# Microcontrollers.net
KiCad netlist of a schematic drawn in Altium Designer
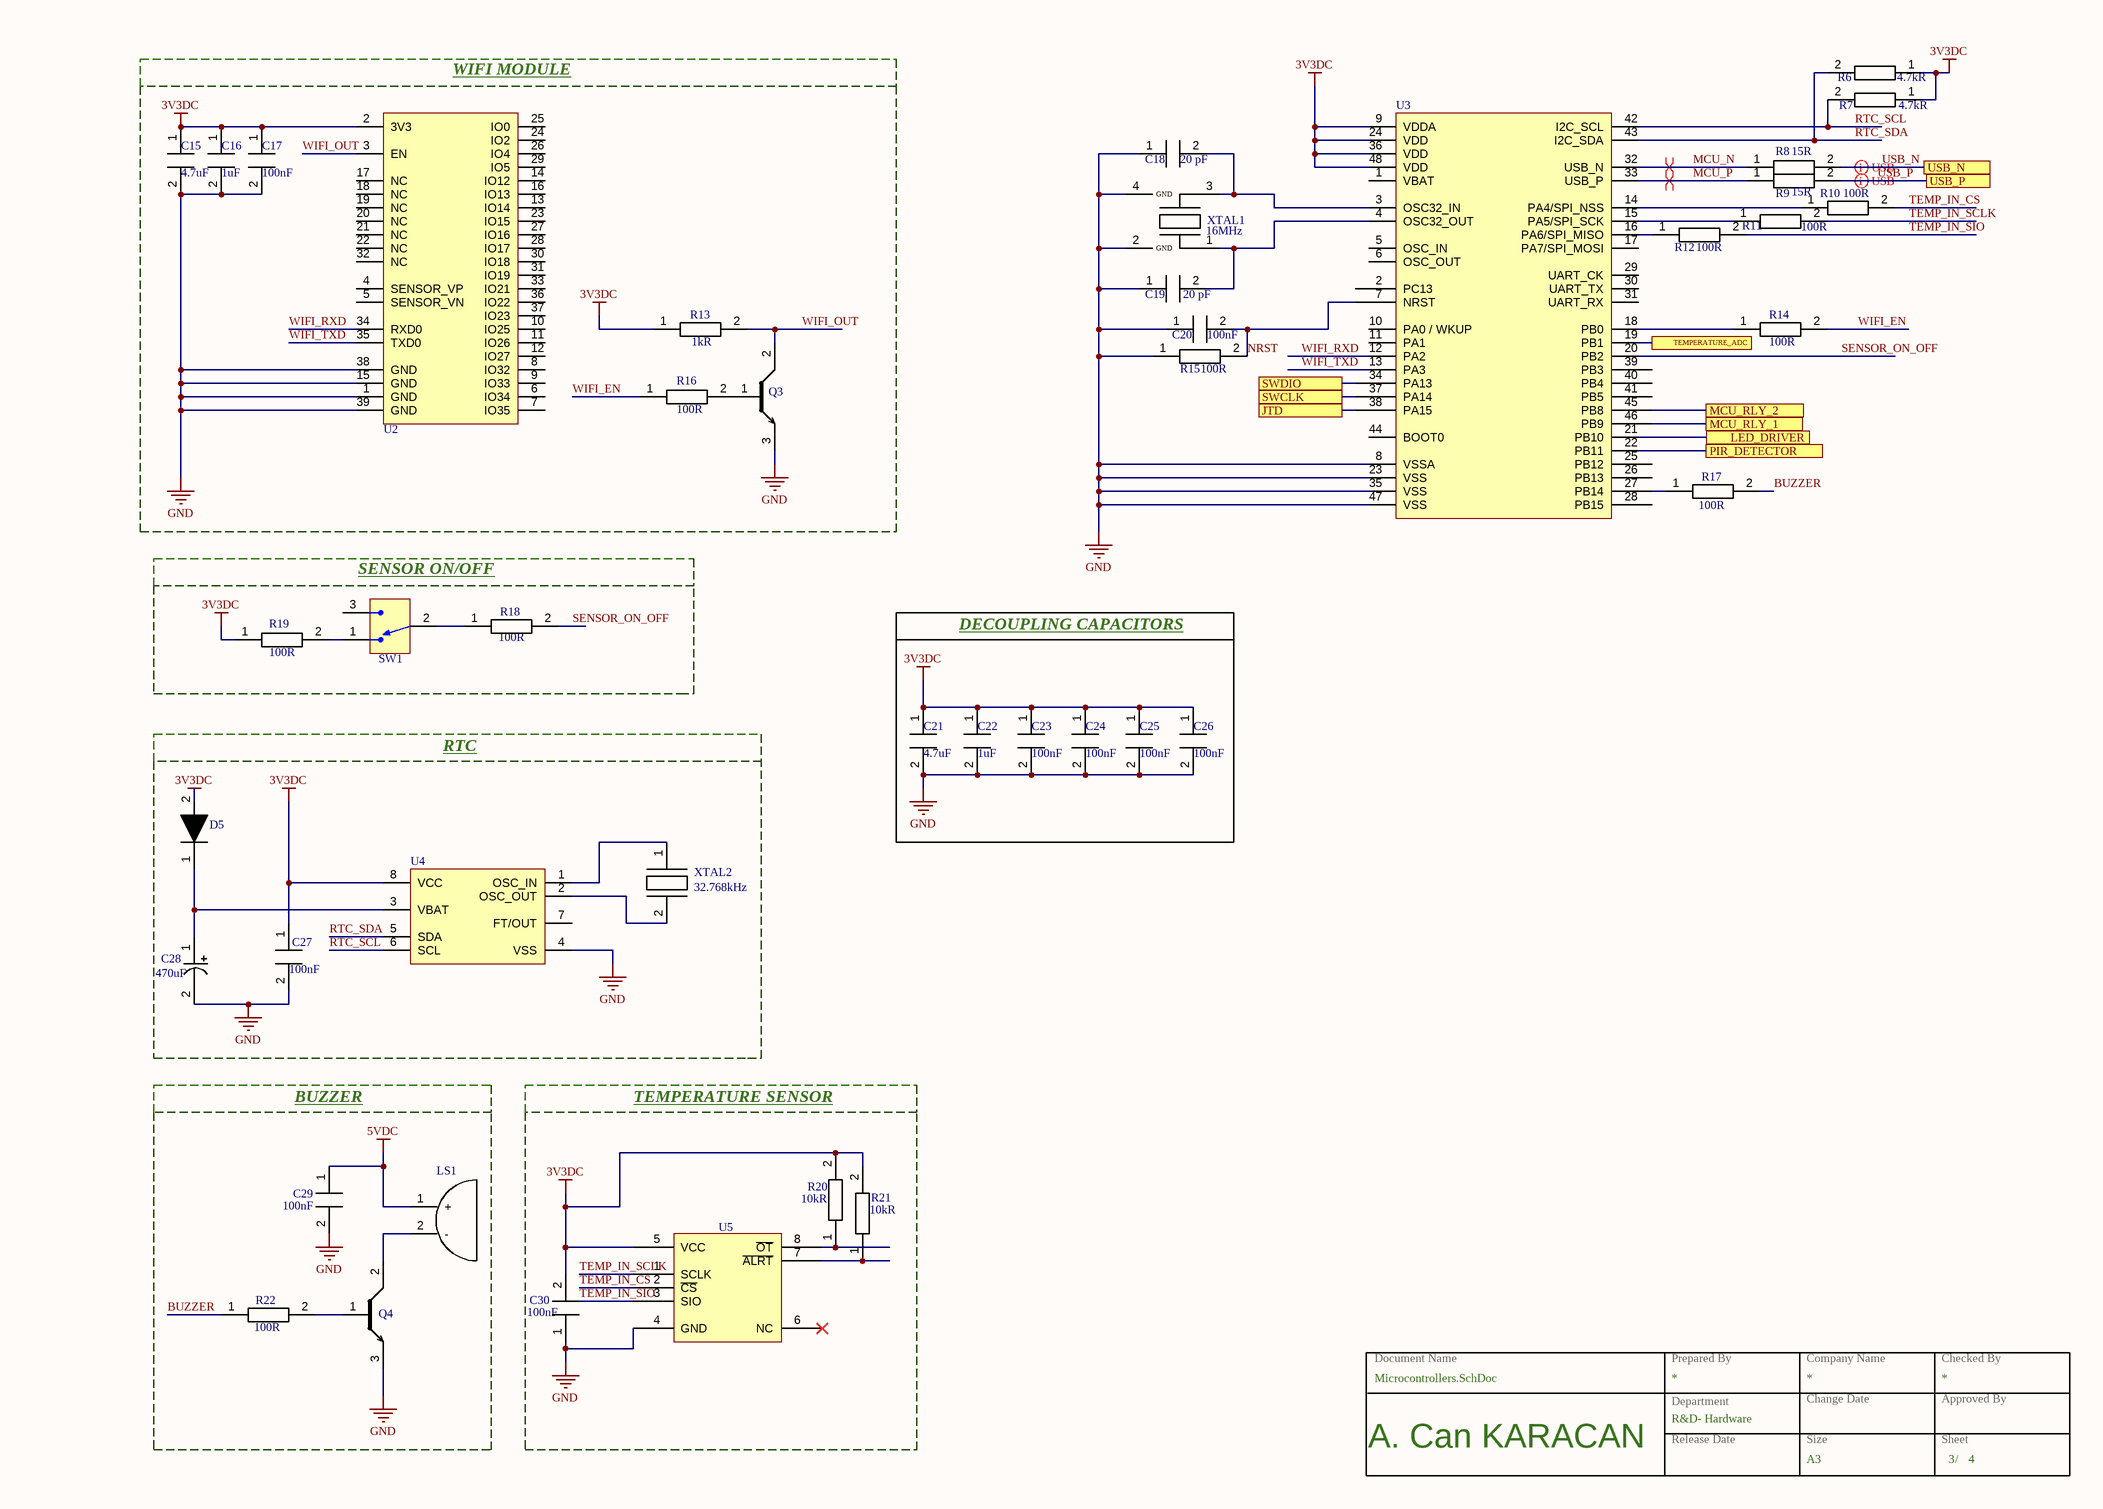
[diagram p0: Microcontrollers.SchDoc]

(export (version "E")
  (design (tool "Eeschema 10.0.6"))
  (components
    (comp (ref "C15")
      (value "4.7uF")
      (footprint "CAP_0805")
      (description "Multilayer Ceramic Capacitor, 4.7 uF, 25 V, ± 10%, X5R, 0805 [2012 Metric]")
      (fields
        (field (name "MANUFACTURER") "Samsung")
        (field (name "MANUFACTURER PART NUMBER") "CL21A475KAQNNNE")
        (field (name "DESIGNED BY") "Ahmet Can")
      )
      (libsource (lib "AHMET_CAN_KARACAN") (part "CAP CER 4.7uF 0805"))
    )
    (comp (ref "C16")
      (value "1uF")
      (footprint "CAP_0805")
      (description "CAP CER %10 1uF 0805")
      (fields
        (field (name "MANUFACTURER") "Samsung")
        (field (name "MANUFACTURER PART NUMBER") "CL21B105KBFNNNE")
      )
      (libsource (lib "AHMET_CAN_KARACAN") (part "CAP CER 1uF 0805"))
    )
    (comp (ref "C17")
      (value "CL21B104KBCNNNC")
      (footprint "CAP_0805")
      (description "Multilayer Ceramic Capacitor, 0.1 uF, 50 V, ± 10%, X7R, 0805 [2012 Metric]")
      (fields
        (field (name "MANUFACTURER") "Samsung")
        (field (name "TOLERANCE") "10%")
        (field (name "CAPACITANCE") "100nF")
      )
      (libsource (lib "AHMET_CAN_KARACAN") (part "CAP CER 100nF 0805"))
    )
    (comp (ref "C18")
      (value "20 pF")
      (footprint "CAP_0603")
      (description "CAP CER 20PF 50V C0G/NP0 0603")
      (fields
        (field (name "MANUFACTURER") "Samsung")
        (field (name "MANUFACTURER PART NUMBER") "CL10C200JB8NNNC")
        (field (name "DESIGNED BY") "Ahmet Can")
      )
      (libsource (lib "AHMET_CAN_KARACAN") (part "CAP CER 20pF 0603"))
    )
    (comp (ref "C19")
      (value "20 pF")
      (footprint "CAP_0603")
      (description "CAP CER 20PF 50V C0G/NP0 0603")
      (fields
        (field (name "MANUFACTURER") "Samsung")
        (field (name "MANUFACTURER PART NUMBER") "CL10C200JB8NNNC")
        (field (name "DESIGNED BY") "Ahmet Can")
      )
      (libsource (lib "AHMET_CAN_KARACAN") (part "CAP CER 20pF 0603"))
    )
    (comp (ref "C20")
      (value "104KBCNNNC")
      (footprint "CAP_0805")
      (description "Multilayer Ceramic Capacitor, 0.1 uF, 50 V, ± 10%, X7R, 0805 [2012 Metric]")
      (fields
        (field (name "MANUFACTURER") "Samsung")
        (field (name "MANUFACTURER PART NUMBER") "CL21B104KBCNNNC")
        (field (name "CAPACITANCE") "100nF")
      )
      (libsource (lib "AHMET_CAN_KARACAN") (part "CAP CER 100nF 0805"))
    )
    (comp (ref "C21")
      (value "4.7uF")
      (footprint "CAP_0805")
      (description "Multilayer Ceramic Capacitor, 4.7 uF, 25 V, ± 10%, X5R, 0805 [2012 Metric]")
      (fields
        (field (name "MANUFACTURER") "Samsung")
        (field (name "MANUFACTURER PART NUMBER") "CL21A475KAQNNNE")
        (field (name "DESIGNED BY") "Ahmet Can")
      )
      (libsource (lib "AHMET_CAN_KARACAN") (part "CAP CER 4.7uF 0805"))
    )
    (comp (ref "C22")
      (value "1uF")
      (footprint "CAP_0805")
      (description "CAP CER %10 1uF 0805")
      (fields
        (field (name "MANUFACTURER") "Samsung")
        (field (name "MANUFACTURER PART NUMBER") "CL21B105KBFNNNE")
      )
      (libsource (lib "AHMET_CAN_KARACAN") (part "CAP CER 1uF 0805"))
    )
    (comp (ref "C23")
      (value "CL21B104KBCNNNC")
      (footprint "CAP_0805")
      (description "Multilayer Ceramic Capacitor, 0.1 uF, 50 V, ± 10%, X7R, 0805 [2012 Metric]")
      (fields
        (field (name "MANUFACTURER") "Samsung")
        (field (name "TOLERANCE") "10%")
        (field (name "CAPACITANCE") "100nF")
      )
      (libsource (lib "AHMET_CAN_KARACAN") (part "CAP CER 100nF 0805"))
    )
    (comp (ref "C24")
      (value "CL21B104KBCNNNC")
      (footprint "CAP_0805")
      (description "Multilayer Ceramic Capacitor, 0.1 uF, 50 V, ± 10%, X7R, 0805 [2012 Metric]")
      (fields
        (field (name "MANUFACTURER") "Samsung")
        (field (name "TOLERANCE") "10%")
        (field (name "CAPACITANCE") "100nF")
      )
      (libsource (lib "AHMET_CAN_KARACAN") (part "CAP CER 100nF 0805"))
    )
    (comp (ref "C25")
      (value "CL21B104KBCNNNC")
      (footprint "CAP_0805")
      (description "Multilayer Ceramic Capacitor, 0.1 uF, 50 V, ± 10%, X7R, 0805 [2012 Metric]")
      (fields
        (field (name "MANUFACTURER") "Samsung")
        (field (name "TOLERANCE") "10%")
        (field (name "CAPACITANCE") "100nF")
      )
      (libsource (lib "AHMET_CAN_KARACAN") (part "CAP CER 100nF 0805"))
    )
    (comp (ref "C26")
      (value "CL21B104KBCNNNC")
      (footprint "CAP_0805")
      (description "Multilayer Ceramic Capacitor, 0.1 uF, 50 V, ± 10%, X7R, 0805 [2012 Metric]")
      (fields
        (field (name "MANUFACTURER") "Samsung")
        (field (name "TOLERANCE") "10%")
        (field (name "CAPACITANCE") "100nF")
      )
      (libsource (lib "AHMET_CAN_KARACAN") (part "CAP CER 100nF 0805"))
    )
    (comp (ref "C27")
      (value "CL21B104KBCNNNC")
      (footprint "CAP_0805")
      (description "Multilayer Ceramic Capacitor, 0.1 uF, 50 V, ± 10%, X7R, 0805 [2012 Metric]")
      (fields
        (field (name "MANUFACTURER") "Samsung")
        (field (name "TOLERANCE") "10%")
        (field (name "CAPACITANCE") "100nF")
        (field (name "DESIGNED BY") "Ahmet Can")
      )
      (libsource (lib "AHMET_CAN_KARACAN") (part "CAP CER 100nF 0805"))
    )
    (comp (ref "C28")
      (value "470uF")
      (footprint "CAP_RADIAL_D10_P5")
      (description "Cap, 470UF, 50V, Alu Elec, Radial, Through Hole")
      (fields
        (field (name "MANUFACTURER") "KEMET")
        (field (name "MANUFACTURER PART NUMBER") "ESH477M050AH4AA")
        (field (name "DESIGNED BY") "Ahmet Can")
      )
      (libsource (lib "AHMET_CAN_KARACAN") (part "CAP ALU ELEC 470uF"))
    )
    (comp (ref "C29")
      (value "CL21B104KBCNNNC")
      (footprint "CAP_0805")
      (description "Multilayer Ceramic Capacitor, 0.1 uF, 50 V, ± 10%, X7R, 0805 [2012 Metric]")
      (fields
        (field (name "MANUFACTURER") "Samsung")
        (field (name "TOLERANCE") "10%")
        (field (name "CAPACITANCE") "100nF")
        (field (name "DESIGNED BY") "Ahmet Can")
      )
      (libsource (lib "AHMET_CAN_KARACAN") (part "CAP CER 100nF 0805"))
    )
    (comp (ref "C30")
      (value "CL21B104KBCNNNC")
      (footprint "CAP_0805")
      (description "Multilayer Ceramic Capacitor, 0.1 uF, 50 V, ± 10%, X7R, 0805 [2012 Metric]")
      (fields
        (field (name "MANUFACTURER") "Samsung")
        (field (name "TOLERANCE") "10%")
        (field (name "CAPACITANCE") "100nF")
        (field (name "DESIGNED BY") "Ahmet Can")
      )
      (libsource (lib "AHMET_CAN_KARACAN") (part "CAP CER 100nF 0805"))
    )
    (comp (ref "D5")
      (value "1N4148WS")
      (footprint "SOD_323_F")
      (description "Diode Ultra Fast Recovery Rectifier 75V 0.15A 2-Pin SOD-323F T/R")
      (fields
        (field (name "MANUFACTURER") "ON Semiconductor / Fairchild")
        (field (name "DESIGNED BY") "Ahmet Can")
      )
      (libsource (lib "AHMET_CAN_KARACAN") (part "DIO_1N4148WS"))
    )
    (comp (ref "LS1")
      (value "CMI-9605-0580T")
      (footprint "CMI-9605")
      (description "9.6 mm, 5 Vdc, 80 dB, Through Hole, Driving Circuit, Magnetic Audio Indicator Buzzer")
      (fields (field (name "MANUFACTURER") "CUI") (field (name "DESIGNED BY") "Ahmet Can"))
      (libsource (lib "AHMET_CAN_KARACAN") (part "LS_CMI-9605-0580T"))
    )
    (comp (ref "Q3")
      (value "MMBT3904-7-F")
      (footprint "SOT_23_3")
      (description "Transistor General Purpose BJT NPN 40 Volt 0.2A Automotive 3-Pin SOT-23-3")
      (fields (field (name "MANUFACTURER") "Diodes Zetex") (field (name "DESIGNED BY") "Ahmet Can"))
      (libsource (lib "AHMET_CAN_KARACAN") (part "Q_MMBT3904-7-F"))
    )
    (comp (ref "Q4")
      (value "MMBT3904-7-F")
      (footprint "SOT_23_3")
      (description "Transistor General Purpose BJT NPN 40 Volt 0.2A Automotive 3-Pin SOT-23-3")
      (fields (field (name "MANUFACTURER") "Diodes Zetex") (field (name "DESIGNED BY") "Ahmet Can"))
      (libsource (lib "AHMET_CAN_KARACAN") (part "Q_MMBT3904-7-F"))
    )
    (comp (ref "R6")
      (value "4.7kR")
      (footprint "RE_0603")
      (description "SMD Chip Resistor, 4.7 kOhm, ± 5%, 100 mW, 0603 [1608 Metric], Thick Film, General Purpose")
      (fields
        (field (name "MANUFACTURER") "Yageo")
        (field (name "MANUFACTURER PART NUMBER") "RC0603JR-074K7L")
        (field (name "DESIGNED BY") "Ahmet Can")
      )
      (libsource (lib "AHMET_CAN_KARACAN") (part "RES 4K7 0603"))
    )
    (comp (ref "R7")
      (value "4.7kR")
      (footprint "RE_0603")
      (description "SMD Chip Resistor, 4.7 kOhm, ± 5%, 100 mW, 0603 [1608 Metric], Thick Film, General Purpose")
      (fields
        (field (name "MANUFACTURER") "Yageo")
        (field (name "MANUFACTURER PART NUMBER") "RC0603JR-074K7L")
        (field (name "DESIGNED BY") "Ahmet Can")
      )
      (libsource (lib "AHMET_CAN_KARACAN") (part "RES 4K7 0603"))
    )
    (comp (ref "R8")
      (value "15R")
      (footprint "RE_0603")
      (description "SMD Chip Resistor, 15 Ohm, ± 5%, 100 mW, 0603 [1608 Metric], Thick Film, General Purpose")
      (fields
        (field (name "MANUFACTURER") "Yageo")
        (field (name "MANUFACTURER PART NUMBER") "RC0603JR-0715RL")
        (field (name "DESIGNED BY") "Ahmet Can")
      )
      (libsource (lib "AHMET_CAN_KARACAN") (part "RES 15 0603"))
    )
    (comp (ref "R9")
      (value "15R")
      (footprint "RE_0603")
      (description "SMD Chip Resistor, 15 Ohm, ± 5%, 100 mW, 0603 [1608 Metric], Thick Film, General Purpose")
      (fields
        (field (name "MANUFACTURER") "Yageo")
        (field (name "MANUFACTURER PART NUMBER") "RC0603JR-0715RL")
        (field (name "DESIGNED BY") "Ahmet Can")
      )
      (libsource (lib "AHMET_CAN_KARACAN") (part "RES 15 0603"))
    )
    (comp (ref "R10")
      (value "100R")
      (footprint "RE_0603")
      (description "Res Thick Film 0603 100 Ohm 5% 1/10W ±100ppm/°C Molded SMD SMD Paper T/R")
      (fields
        (field (name "MANUFACTURER") "Yageo")
        (field (name "MANUFACTURER PART NUMBER") "RC0603JR-07100RL")
        (field (name "DESIGNED BY") "Ahmet Can")
      )
      (libsource (lib "AHMET_CAN_KARACAN") (part "RES 100 0603"))
    )
    (comp (ref "R11")
      (value "100R")
      (footprint "RE_0603")
      (description "Res Thick Film 0603 100 Ohm 5% 1/10W ±100ppm/°C Molded SMD SMD Paper T/R")
      (fields
        (field (name "MANUFACTURER") "Yageo")
        (field (name "MANUFACTURER PART NUMBER") "RC0603JR-07100RL")
        (field (name "DESIGNED BY") "Ahmet Can")
      )
      (libsource (lib "AHMET_CAN_KARACAN") (part "RES 100 0603"))
    )
    (comp (ref "R12")
      (value "100R")
      (footprint "RE_0603")
      (description "Res Thick Film 0603 100 Ohm 5% 1/10W ±100ppm/°C Molded SMD SMD Paper T/R")
      (fields
        (field (name "MANUFACTURER") "Yageo")
        (field (name "MANUFACTURER PART NUMBER") "RC0603JR-07100RL")
        (field (name "DESIGNED BY") "Ahmet Can")
      )
      (libsource (lib "AHMET_CAN_KARACAN") (part "RES 100 0603"))
    )
    (comp (ref "R13")
      (value "1kR")
      (footprint "RE_0603")
      (description "SMD Chip Resistor, 1 kOhm, ± 1%, 63 mW, 0402 [1005 Metric], Thick Film, General Purpose")
      (fields
        (field (name "MANUFACTURER") "Yageo")
        (field (name "MANUFACTURER PART NUMBER") "RC0402FR-071KL")
        (field (name "DESIGNED BY") "Ahmet Can")
      )
      (libsource (lib "AHMET_CAN_KARACAN") (part "RES 1K 0603"))
    )
    (comp (ref "R14")
      (value "100R")
      (footprint "RE_0603")
      (description "Res Thick Film 0603 100 Ohm 5% 1/10W ±100ppm/°C Molded SMD SMD Paper T/R")
      (fields
        (field (name "MANUFACTURER") "Yageo")
        (field (name "MANUFACTURER PART NUMBER") "RC0603JR-07100RL")
        (field (name "DESIGNED BY") "Ahmet Can")
      )
      (libsource (lib "AHMET_CAN_KARACAN") (part "RES 100 0603"))
    )
    (comp (ref "R15")
      (value "100R")
      (footprint "RE_0603")
      (description "Res Thick Film 0603 100 Ohm 5% 1/10W ±100ppm/°C Molded SMD SMD Paper T/R")
      (fields
        (field (name "MANUFACTURER") "Yageo")
        (field (name "MANUFACTURER PART NUMBER") "RC0603JR-07100RL")
        (field (name "DESIGNED BY") "Ahmet Can")
      )
      (libsource (lib "AHMET_CAN_KARACAN") (part "RES 100 0603"))
    )
    (comp (ref "R16")
      (value "100R")
      (footprint "RE_0603")
      (description "Res Thick Film 0603 100 Ohm 5% 1/10W ±100ppm/°C Molded SMD SMD Paper T/R")
      (fields
        (field (name "MANUFACTURER") "Yageo")
        (field (name "MANUFACTURER PART NUMBER") "RC0603JR-07100RL")
        (field (name "DESIGNED BY") "Ahmet Can")
      )
      (libsource (lib "AHMET_CAN_KARACAN") (part "RES 100 0603"))
    )
    (comp (ref "R17")
      (value "100R")
      (footprint "RE_0603")
      (description "Res Thick Film 0603 100 Ohm 5% 1/10W ±100ppm/°C Molded SMD SMD Paper T/R")
      (fields
        (field (name "MANUFACTURER") "Yageo")
        (field (name "MANUFACTURER PART NUMBER") "RC0603JR-07100RL")
        (field (name "DESIGNED BY") "Ahmet Can")
      )
      (libsource (lib "AHMET_CAN_KARACAN") (part "RES 100 0603"))
    )
    (comp (ref "R18")
      (value "100R")
      (footprint "RE_0603")
      (description "Res Thick Film 0603 100 Ohm 5% 1/10W ±100ppm/°C Molded SMD SMD Paper T/R")
      (fields
        (field (name "MANUFACTURER") "Yageo")
        (field (name "MANUFACTURER PART NUMBER") "RC0603JR-07100RL")
        (field (name "DESIGNED BY") "Ahmet Can")
      )
      (libsource (lib "AHMET_CAN_KARACAN") (part "RES 100 0603"))
    )
    (comp (ref "R19")
      (value "100R")
      (footprint "RE_0603")
      (description "Res Thick Film 0603 100 Ohm 5% 1/10W ±100ppm/°C Molded SMD SMD Paper T/R")
      (fields
        (field (name "MANUFACTURER") "Yageo")
        (field (name "MANUFACTURER PART NUMBER") "RC0603JR-07100RL")
        (field (name "DESIGNED BY") "Ahmet Can")
      )
      (libsource (lib "AHMET_CAN_KARACAN") (part "RES 100 0603"))
    )
    (comp (ref "R20")
      (value "10kR")
      (footprint "RE_0402")
      (description "SMD Chip Resistor, 10 kOhm, ± 5%, 63 mW, 0402 [1005 Metric], Thick Film, General Purpose")
      (fields
        (field (name "MANUFACTURER") "Yageo")
        (field (name "MANUFACTURER PART NUMBER") "RC0402JR-0710KL")
        (field (name "DESIGNED BY") "Ahmet Can")
      )
      (libsource (lib "AHMET_CAN_KARACAN") (part "RES 10K 0402"))
    )
    (comp (ref "R21")
      (value "10kR")
      (footprint "RE_0402")
      (description "SMD Chip Resistor, 10 kOhm, ± 5%, 63 mW, 0402 [1005 Metric], Thick Film, General Purpose")
      (fields
        (field (name "MANUFACTURER") "Yageo")
        (field (name "MANUFACTURER PART NUMBER") "RC0402JR-0710KL")
        (field (name "DESIGNED BY") "Ahmet Can")
      )
      (libsource (lib "AHMET_CAN_KARACAN") (part "RES 10K 0402"))
    )
    (comp (ref "R22")
      (value "100R")
      (footprint "RE_0603")
      (description "Res Thick Film 0603 100 Ohm 5% 1/10W ±100ppm/°C Molded SMD SMD Paper T/R")
      (fields
        (field (name "MANUFACTURER") "Yageo")
        (field (name "MANUFACTURER PART NUMBER") "RC0603JR-07100RL")
        (field (name "DESIGNED BY") "Ahmet Can")
      )
      (libsource (lib "AHMET_CAN_KARACAN") (part "RES 100 0603"))
    )
    (comp (ref "SW1")
      (value "EG1215AA")
      (footprint "EG1215AA")
      (description "Slide Switch, SPDT, 0.025A, 24V, SMD")
      (fields (field (name "MANUFACTURER") "E-Switch") (field (name "DESIGNED BY") "Ahmet Can"))
      (libsource (lib "AHMET_CAN_KARACAN") (part "SW_EG1215AA"))
    )
    (comp (ref "U2")
      (value "ESP32-WROOM-32E-N4")
      (footprint "38_SMD")
      (description "SMD module, ESP32-D0WD-V3, ESP32 ECO V3, 4 MB SPI flash, PCB antenna")
      (fields
        (field (name "MANUFACTURER") "Espressif Systems")
        (field (name "MANUFACTURER PART NUMBER") "ESP32-WROOM-32E(M113EH3200PH3Q0)")
        (field (name "DESIGNED BY") "Ahmet Can")
      )
      (libsource (lib "AHMET_CAN_KARACAN") (part "U_ESP32-WROOM-32E-N4"))
    )
    (comp (ref "U3")
      (value "STM32F103C6T6A")
      (footprint "LQGP48-STM")
      (description "MCU 32-bit STM32F ARM Cortex M3 RISC 32KB Flash 2.5V/3.3V 48-Pin LQFP Tray")
      (fields (field (name "MANUFACTURER") "STMicroelectronics") (field (name "DESIGNED BY") "Ahmet Can"))
      (libsource (lib "AHMET_CAN_KARACAN") (part "U_STM32F103C6T6A"))
    )
    (comp (ref "U4")
      (value "M41T0M6F")
      (footprint "8_SOIC")
      (description "M41T0 Series 2 to 5.5 V Serial I2C Real Time Clock Surface Mount - SOIC-8")
      (fields (field (name "MANUFACTURER") "STMicroelectronics") (field (name "DESIGNEDBY") "Ahmet Can"))
      (libsource (lib "AHMET_CAN_KARACAN") (part "RTC_M41T0M6F"))
    )
    (comp (ref "U5")
      (value "MAX6662MSA+")
      (footprint "8_SOIC")
      (description "Temp Sensor Digital Serial (3-Wire, SPI) 8-Pin SOIC N Tube")
      (fields (field (name "MANUFACTURER") "Maxim") (field (name "DESIGNED BY") "Ahmet Can"))
      (libsource (lib "AHMET_CAN_KARACAN") (part "U_MAX6662MSA+"))
    )
    (comp (ref "XTAL1")
      (value "ECS-160-20-30B-TR")
      (footprint "4-SMD, No Lead")
      (description "Crystal 16MHz ±30ppm (Tol) ±100ppm (Stability) 20pF FUND 50Ohm 4-Pin SMD T/R")
      (fields
        (field (name "MANUFACTURER") "ECS International")
        (field (name "MANUFACTURER PART NUMBER") "ECS-160-20-30B-DU")
        (field (name "FREQUENCY") "16MHz")
        (field (name "DESIGNED BY") "Ahmet Can")
      )
      (libsource (lib "AHMET_CAN_KARACAN") (part "XTAL_CRYSTAL 16 MHz"))
    )
    (comp (ref "XTAL2")
      (value "ABS05-32.768KHZ-T")
      (footprint "2-SMD, No Lead")
      (description "CRYSTAL 32.768kHz ±20ppm Crystal 12.5pF 90 kOhm -40°C ^ 85°C Surface Mount 2-SMD")
      (fields
        (field (name "MANUFACTURER") "Abracon")
        (field (name "TOLERANCE") "20ppm")
        (field (name "FREQUENCY") "32.768kHz")
        (field (name "DESIGNED BY") "Ahmet Can")
      )
      (libsource (lib "AHMET_CAN_KARACAN") (part "XTAL_CRYSTAL 32.768 KHz"))
    )
  )
  (nets
    (net (code "1") (name "/BUZZER") (class "Default")
      (node (ref "R17") (pin "2") (pintype "passive"))
      (node (ref "R22") (pin "1") (pintype "passive"))
    )
    (net (code "2") (name "/JTD") (class "Default")
      (node (ref "U3") (pin "38") (pinfunction "PA15_38") (pintype "passive"))
    )
    (net (code "3") (name "/LED_DRIVER") (class "Default")
      (node (ref "U3") (pin "21") (pinfunction "PB10_21") (pintype "passive"))
    )
    (net (code "4") (name "/MCU_N") (class "Default")
      (node (ref "R8") (pin "1") (pintype "passive"))
      (node (ref "U3") (pin "32") (pinfunction "USB_N_32") (pintype "passive"))
    )
    (net (code "5") (name "/MCU_P") (class "Default")
      (node (ref "R9") (pin "1") (pintype "passive"))
      (node (ref "U3") (pin "33") (pinfunction "USB_P_33") (pintype "passive"))
    )
    (net (code "6") (name "/MCU_RLY_1") (class "Default")
      (node (ref "U3") (pin "46") (pinfunction "PB9_46") (pintype "passive"))
    )
    (net (code "7") (name "/MCU_RLY_2") (class "Default")
      (node (ref "U3") (pin "45") (pinfunction "PB8_45") (pintype "passive"))
    )
    (net (code "8") (name "/NRST") (class "Default")
      (node (ref "C20") (pin "2") (pintype "passive"))
      (node (ref "R15") (pin "2") (pintype "passive"))
      (node (ref "U3") (pin "7") (pinfunction "NRST_7") (pintype "passive"))
    )
    (net (code "9") (name "/PIR_DETECTOR") (class "Default")
      (node (ref "U3") (pin "22") (pinfunction "PB11_22") (pintype "passive"))
    )
    (net (code "10") (name "/RTC_SCL") (class "Default")
      (node (ref "R7") (pin "2") (pintype "passive"))
      (node (ref "U3") (pin "42") (pinfunction "I2C_SCL_42") (pintype "passive"))
      (node (ref "U4") (pin "6") (pinfunction "SCL_6") (pintype "passive"))
    )
    (net (code "11") (name "/RTC_SDA") (class "Default")
      (node (ref "R6") (pin "2") (pintype "passive"))
      (node (ref "U3") (pin "43") (pinfunction "I2C_SDA_43") (pintype "passive"))
      (node (ref "U4") (pin "5") (pinfunction "SDA_5") (pintype "passive"))
    )
    (net (code "12") (name "/SENSOR_ON_OFF") (class "Default")
      (node (ref "R18") (pin "2") (pintype "passive"))
      (node (ref "U3") (pin "20") (pinfunction "PB2_20") (pintype "passive"))
    )
    (net (code "13") (name "/SWCLK") (class "Default")
      (node (ref "U3") (pin "37") (pinfunction "PA14_37") (pintype "passive"))
    )
    (net (code "14") (name "/SWDIO") (class "Default")
      (node (ref "U3") (pin "34") (pinfunction "PA13_34") (pintype "passive"))
    )
    (net (code "15") (name "/TEMPERATURE_ADC") (class "Default")
      (node (ref "U3") (pin "19") (pinfunction "PB1_19") (pintype "passive"))
    )
    (net (code "16") (name "/TEMP_IN_CS") (class "Default")
      (node (ref "R10") (pin "2") (pintype "passive"))
      (node (ref "U5") (pin "2") (pinfunction "~{CS}_2") (pintype "passive"))
    )
    (net (code "17") (name "/TEMP_IN_SCLK") (class "Default")
      (node (ref "R11") (pin "2") (pintype "passive"))
      (node (ref "U5") (pin "1") (pinfunction "SCLK_1") (pintype "passive"))
    )
    (net (code "18") (name "/TEMP_IN_SIO") (class "Default")
      (node (ref "R12") (pin "2") (pintype "passive"))
      (node (ref "U5") (pin "3") (pinfunction "SIO_3") (pintype "passive"))
    )
    (net (code "19") (name "/USB_N") (class "Default") (node (ref "R8") (pin "2") (pintype "passive")))
    (net (code "20") (name "/USB_P") (class "Default") (node (ref "R9") (pin "2") (pintype "passive")))
    (net (code "21") (name "/WIFI_EN") (class "Default")
      (node (ref "R14") (pin "2") (pintype "passive"))
      (node (ref "R16") (pin "1") (pintype "passive"))
    )
    (net (code "22") (name "/WIFI_OUT") (class "Default")
      (node (ref "Q3") (pin "2") (pintype "passive"))
      (node (ref "R13") (pin "2") (pintype "passive"))
      (node (ref "U2") (pin "3") (pinfunction "EN_3") (pintype "passive"))
    )
    (net (code "23") (name "/WIFI_RXD") (class "Default")
      (node (ref "U2") (pin "34") (pinfunction "RXD0_34") (pintype "passive"))
      (node (ref "U3") (pin "12") (pinfunction "PA2_12") (pintype "passive"))
    )
    (net (code "24") (name "/WIFI_TXD") (class "Default")
      (node (ref "U2") (pin "35") (pinfunction "TXD0_35") (pintype "passive"))
      (node (ref "U3") (pin "13") (pinfunction "PA3_13") (pintype "passive"))
    )
    (net (code "25") (name "3V3DC") (class "Default")
      (node (ref "C15") (pin "1") (pintype "passive"))
      (node (ref "C16") (pin "1") (pintype "passive"))
      (node (ref "C17") (pin "1") (pintype "passive"))
      (node (ref "C21") (pin "1") (pintype "passive"))
      (node (ref "C22") (pin "1") (pintype "passive"))
      (node (ref "C23") (pin "1") (pintype "passive"))
      (node (ref "C24") (pin "1") (pintype "passive"))
      (node (ref "C25") (pin "1") (pintype "passive"))
      (node (ref "C26") (pin "1") (pintype "passive"))
      (node (ref "C27") (pin "1") (pintype "passive"))
      (node (ref "C30") (pin "2") (pintype "passive"))
      (node (ref "D5") (pin "2") (pintype "passive"))
      (node (ref "R13") (pin "1") (pintype "passive"))
      (node (ref "R19") (pin "1") (pintype "passive"))
      (node (ref "R20") (pin "2") (pintype "passive"))
      (node (ref "R21") (pin "2") (pintype "passive"))
      (node (ref "R6") (pin "1") (pintype "passive"))
      (node (ref "R7") (pin "1") (pintype "passive"))
      (node (ref "U2") (pin "2") (pinfunction "3V3_2") (pintype "passive"))
      (node (ref "U3") (pin "24") (pinfunction "VDD_24") (pintype "passive"))
      (node (ref "U3") (pin "36") (pinfunction "VDD_36") (pintype "passive"))
      (node (ref "U3") (pin "48") (pinfunction "VDD_48") (pintype "passive"))
      (node (ref "U3") (pin "9") (pinfunction "VDDA_9") (pintype "passive"))
      (node (ref "U4") (pin "8") (pinfunction "VCC_8") (pintype "passive"))
      (node (ref "U5") (pin "5") (pinfunction "VCC_5") (pintype "passive"))
    )
    (net (code "26") (name "5VDC") (class "Default")
      (node (ref "C29") (pin "1") (pintype "passive"))
      (node (ref "LS1") (pin "1") (pinfunction "+_1") (pintype "passive"))
    )
    (net (code "27") (name "GND") (class "Default")
      (node (ref "C15") (pin "2") (pintype "passive"))
      (node (ref "C16") (pin "2") (pintype "passive"))
      (node (ref "C17") (pin "2") (pintype "passive"))
      (node (ref "C18") (pin "1") (pintype "passive"))
      (node (ref "C19") (pin "1") (pintype "passive"))
      (node (ref "C20") (pin "1") (pintype "passive"))
      (node (ref "C21") (pin "2") (pintype "passive"))
      (node (ref "C22") (pin "2") (pintype "passive"))
      (node (ref "C23") (pin "2") (pintype "passive"))
      (node (ref "C24") (pin "2") (pintype "passive"))
      (node (ref "C25") (pin "2") (pintype "passive"))
      (node (ref "C26") (pin "2") (pintype "passive"))
      (node (ref "C27") (pin "2") (pintype "passive"))
      (node (ref "C28") (pin "2") (pintype "passive"))
      (node (ref "C29") (pin "2") (pintype "passive"))
      (node (ref "C30") (pin "1") (pintype "passive"))
      (node (ref "Q3") (pin "3") (pintype "passive"))
      (node (ref "Q4") (pin "3") (pintype "passive"))
      (node (ref "R15") (pin "1") (pintype "passive"))
      (node (ref "U2") (pin "1") (pinfunction "GND_1") (pintype "passive"))
      (node (ref "U2") (pin "15") (pinfunction "GND_15") (pintype "passive"))
      (node (ref "U2") (pin "38") (pinfunction "GND_38") (pintype "passive"))
      (node (ref "U2") (pin "39") (pinfunction "GND_39") (pintype "passive"))
      (node (ref "U3") (pin "23") (pinfunction "VSS_23") (pintype "passive"))
      (node (ref "U3") (pin "35") (pinfunction "VSS_35") (pintype "passive"))
      (node (ref "U3") (pin "47") (pinfunction "VSS_47") (pintype "passive"))
      (node (ref "U3") (pin "8") (pinfunction "VSSA_8") (pintype "passive"))
      (node (ref "U4") (pin "4") (pinfunction "VSS_4") (pintype "passive"))
      (node (ref "U5") (pin "4") (pinfunction "GND_4") (pintype "passive"))
      (node (ref "XTAL1") (pin "2") (pinfunction "GND_2") (pintype "passive"))
      (node (ref "XTAL1") (pin "4") (pinfunction "GND_4") (pintype "passive"))
    )
    (net (code "28") (name "Net-(LS1--)") (class "Default")
      (node (ref "LS1") (pin "2") (pinfunction "-_2") (pintype "passive"))
      (node (ref "Q4") (pin "2") (pintype "passive"))
    )
    (net (code "29") (name "Net-(Q3-Pad1)") (class "Default")
      (node (ref "Q3") (pin "1") (pintype "passive"))
      (node (ref "R16") (pin "2") (pintype "passive"))
    )
    (net (code "30") (name "Net-(Q4-Pad1)") (class "Default")
      (node (ref "Q4") (pin "1") (pintype "passive"))
      (node (ref "R22") (pin "2") (pintype "passive"))
    )
    (net (code "31") (name "Net-(R18-Pad1)") (class "Default")
      (node (ref "R18") (pin "1") (pintype "passive"))
      (node (ref "SW1") (pin "2") (pintype "passive"))
    )
    (net (code "32") (name "Net-(R19-Pad2)") (class "Default")
      (node (ref "R19") (pin "2") (pintype "passive"))
      (node (ref "SW1") (pin "1") (pintype "passive"))
    )
    (net (code "33") (name "Net-(U3-OSC32_IN)") (class "Default")
      (node (ref "C18") (pin "2") (pintype "passive"))
      (node (ref "U3") (pin "3") (pinfunction "OSC32_IN_3") (pintype "passive"))
      (node (ref "XTAL1") (pin "3") (pintype "passive"))
    )
    (net (code "34") (name "Net-(U3-OSC32_OUT)") (class "Default")
      (node (ref "C19") (pin "2") (pintype "passive"))
      (node (ref "U3") (pin "4") (pinfunction "OSC32_OUT_4") (pintype "passive"))
      (node (ref "XTAL1") (pin "1") (pintype "passive"))
    )
    (net (code "35") (name "Net-(U3-PA4{slash}SPI_NSS)") (class "Default")
      (node (ref "R10") (pin "1") (pintype "passive"))
      (node (ref "U3") (pin "14") (pinfunction "PA4/SPI_NSS_14") (pintype "passive"))
    )
    (net (code "36") (name "Net-(U3-PA5{slash}SPI_SCK)") (class "Default")
      (node (ref "R11") (pin "1") (pintype "passive"))
      (node (ref "U3") (pin "15") (pinfunction "PA5/SPI_SCK_15") (pintype "passive"))
    )
    (net (code "37") (name "Net-(U3-PA6{slash}SPI_MISO)") (class "Default")
      (node (ref "R12") (pin "1") (pintype "passive"))
      (node (ref "U3") (pin "16") (pinfunction "PA6/SPI_MISO_16") (pintype "passive"))
    )
    (net (code "38") (name "Net-(U3-PB0)") (class "Default")
      (node (ref "R14") (pin "1") (pintype "passive"))
      (node (ref "U3") (pin "18") (pinfunction "PB0_18") (pintype "passive"))
    )
    (net (code "39") (name "Net-(U3-PB14)") (class "Default")
      (node (ref "R17") (pin "1") (pintype "passive"))
      (node (ref "U3") (pin "27") (pinfunction "PB14_27") (pintype "passive"))
    )
    (net (code "40") (name "Net-(U4-OSC_IN)") (class "Default")
      (node (ref "U4") (pin "1") (pinfunction "OSC_IN_1") (pintype "passive"))
      (node (ref "XTAL2") (pin "1") (pintype "passive"))
    )
    (net (code "41") (name "Net-(U4-OSC_OUT)") (class "Default")
      (node (ref "U4") (pin "2") (pinfunction "OSC_OUT_2") (pintype "passive"))
      (node (ref "XTAL2") (pin "2") (pintype "passive"))
    )
    (net (code "42") (name "Net-(U4-VBAT)") (class "Default")
      (node (ref "C28") (pin "1") (pintype "passive"))
      (node (ref "D5") (pin "1") (pintype "passive"))
      (node (ref "U4") (pin "3") (pinfunction "VBAT_3") (pintype "passive"))
    )
    (net (code "43") (name "Net-(U5-~{ALRT})") (class "Default")
      (node (ref "R21") (pin "1") (pintype "passive"))
      (node (ref "U5") (pin "7") (pinfunction "~{ALRT}_7") (pintype "passive"))
    )
    (net (code "44") (name "Net-(U5-~{OT})") (class "Default")
      (node (ref "R20") (pin "1") (pintype "passive"))
      (node (ref "U5") (pin "8") (pinfunction "~{OT}_8") (pintype "passive"))
    )
    (net (code "45") (name "unconnected-(SW1-Pad3)") (class "Default")
      (node (ref "SW1") (pin "3") (pintype "passive"))
    )
    (net (code "46") (name "unconnected-(U2-IO0-Pad25)") (class "Default")
      (node (ref "U2") (pin "25") (pinfunction "IO0_25") (pintype "passive"))
    )
    (net (code "47") (name "unconnected-(U2-IO2-Pad24)") (class "Default")
      (node (ref "U2") (pin "24") (pinfunction "IO2_24") (pintype "passive"))
    )
    (net (code "48") (name "unconnected-(U2-IO4-Pad26)") (class "Default")
      (node (ref "U2") (pin "26") (pinfunction "IO4_26") (pintype "passive"))
    )
    (net (code "49") (name "unconnected-(U2-IO5-Pad29)") (class "Default")
      (node (ref "U2") (pin "29") (pinfunction "IO5_29") (pintype "passive"))
    )
    (net (code "50") (name "unconnected-(U2-IO12-Pad14)") (class "Default")
      (node (ref "U2") (pin "14") (pinfunction "IO12_14") (pintype "passive"))
    )
    (net (code "51") (name "unconnected-(U2-IO13-Pad16)") (class "Default")
      (node (ref "U2") (pin "16") (pinfunction "IO13_16") (pintype "passive"))
    )
    (net (code "52") (name "unconnected-(U2-IO14-Pad13)") (class "Default")
      (node (ref "U2") (pin "13") (pinfunction "IO14_13") (pintype "passive"))
    )
    (net (code "53") (name "unconnected-(U2-IO15-Pad23)") (class "Default")
      (node (ref "U2") (pin "23") (pinfunction "IO15_23") (pintype "passive"))
    )
    (net (code "54") (name "unconnected-(U2-IO16-Pad27)") (class "Default")
      (node (ref "U2") (pin "27") (pinfunction "IO16_27") (pintype "passive"))
    )
    (net (code "55") (name "unconnected-(U2-IO17-Pad28)") (class "Default")
      (node (ref "U2") (pin "28") (pinfunction "IO17_28") (pintype "passive"))
    )
    (net (code "56") (name "unconnected-(U2-IO18-Pad30)") (class "Default")
      (node (ref "U2") (pin "30") (pinfunction "IO18_30") (pintype "passive"))
    )
    (net (code "57") (name "unconnected-(U2-IO19-Pad31)") (class "Default")
      (node (ref "U2") (pin "31") (pinfunction "IO19_31") (pintype "passive"))
    )
    (net (code "58") (name "unconnected-(U2-IO21-Pad33)") (class "Default")
      (node (ref "U2") (pin "33") (pinfunction "IO21_33") (pintype "passive"))
    )
    (net (code "59") (name "unconnected-(U2-IO22-Pad36)") (class "Default")
      (node (ref "U2") (pin "36") (pinfunction "IO22_36") (pintype "passive"))
    )
    (net (code "60") (name "unconnected-(U2-IO23-Pad37)") (class "Default")
      (node (ref "U2") (pin "37") (pinfunction "IO23_37") (pintype "passive"))
    )
    (net (code "61") (name "unconnected-(U2-IO25-Pad10)") (class "Default")
      (node (ref "U2") (pin "10") (pinfunction "IO25_10") (pintype "passive"))
    )
    (net (code "62") (name "unconnected-(U2-IO26-Pad11)") (class "Default")
      (node (ref "U2") (pin "11") (pinfunction "IO26_11") (pintype "passive"))
    )
    (net (code "63") (name "unconnected-(U2-IO27-Pad12)") (class "Default")
      (node (ref "U2") (pin "12") (pinfunction "IO27_12") (pintype "passive"))
    )
    (net (code "64") (name "unconnected-(U2-IO32-Pad8)") (class "Default")
      (node (ref "U2") (pin "8") (pinfunction "IO32_8") (pintype "passive"))
    )
    (net (code "65") (name "unconnected-(U2-IO33-Pad9)") (class "Default")
      (node (ref "U2") (pin "9") (pinfunction "IO33_9") (pintype "passive"))
    )
    (net (code "66") (name "unconnected-(U2-IO34-Pad6)") (class "Default")
      (node (ref "U2") (pin "6") (pinfunction "IO34_6") (pintype "passive"))
    )
    (net (code "67") (name "unconnected-(U2-IO35-Pad7)") (class "Default")
      (node (ref "U2") (pin "7") (pinfunction "IO35_7") (pintype "passive"))
    )
    (net (code "68") (name "unconnected-(U2-NC-Pad17)") (class "Default")
      (node (ref "U2") (pin "17") (pinfunction "NC_17") (pintype "passive"))
    )
    (net (code "69") (name "unconnected-(U2-NC-Pad18)") (class "Default")
      (node (ref "U2") (pin "18") (pinfunction "NC_18") (pintype "passive"))
    )
    (net (code "70") (name "unconnected-(U2-NC-Pad19)") (class "Default")
      (node (ref "U2") (pin "19") (pinfunction "NC_19") (pintype "passive"))
    )
    (net (code "71") (name "unconnected-(U2-NC-Pad20)") (class "Default")
      (node (ref "U2") (pin "20") (pinfunction "NC_20") (pintype "passive"))
    )
    (net (code "72") (name "unconnected-(U2-NC-Pad21)") (class "Default")
      (node (ref "U2") (pin "21") (pinfunction "NC_21") (pintype "passive"))
    )
    (net (code "73") (name "unconnected-(U2-NC-Pad22)") (class "Default")
      (node (ref "U2") (pin "22") (pinfunction "NC_22") (pintype "passive"))
    )
    (net (code "74") (name "unconnected-(U2-NC-Pad32)") (class "Default")
      (node (ref "U2") (pin "32") (pinfunction "NC_32") (pintype "passive"))
    )
    (net (code "75") (name "unconnected-(U2-SENSOR_VN-Pad5)") (class "Default")
      (node (ref "U2") (pin "5") (pinfunction "SENSOR_VN_5") (pintype "passive"))
    )
    (net (code "76") (name "unconnected-(U2-SENSOR_VP-Pad4)") (class "Default")
      (node (ref "U2") (pin "4") (pinfunction "SENSOR_VP_4") (pintype "passive"))
    )
    (net (code "77") (name "unconnected-(U3-BOOT0-Pad44)") (class "Default")
      (node (ref "U3") (pin "44") (pinfunction "BOOT0_44") (pintype "passive"))
    )
    (net (code "78") (name "unconnected-(U3-OSC_IN-Pad5)") (class "Default")
      (node (ref "U3") (pin "5") (pinfunction "OSC_IN_5") (pintype "passive"))
    )
    (net (code "79") (name "unconnected-(U3-OSC_OUT-Pad6)") (class "Default")
      (node (ref "U3") (pin "6") (pinfunction "OSC_OUT_6") (pintype "passive"))
    )
    (net (code "80") (name "unconnected-(U3-PA0_{slash}_WKUP-Pad10)") (class "Default")
      (node (ref "U3") (pin "10") (pinfunction "PA0_/_WKUP_10") (pintype "passive"))
    )
    (net (code "81") (name "unconnected-(U3-PA1-Pad11)") (class "Default")
      (node (ref "U3") (pin "11") (pinfunction "PA1_11") (pintype "passive"))
    )
    (net (code "82") (name "unconnected-(U3-PA7{slash}SPI_MOSI-Pad17)") (class "Default")
      (node (ref "U3") (pin "17") (pinfunction "PA7/SPI_MOSI_17") (pintype "passive"))
    )
    (net (code "83") (name "unconnected-(U3-PB3-Pad39)") (class "Default")
      (node (ref "U3") (pin "39") (pinfunction "PB3_39") (pintype "passive"))
    )
    (net (code "84") (name "unconnected-(U3-PB4-Pad40)") (class "Default")
      (node (ref "U3") (pin "40") (pinfunction "PB4_40") (pintype "passive"))
    )
    (net (code "85") (name "unconnected-(U3-PB5-Pad41)") (class "Default")
      (node (ref "U3") (pin "41") (pinfunction "PB5_41") (pintype "passive"))
    )
    (net (code "86") (name "unconnected-(U3-PB12-Pad25)") (class "Default")
      (node (ref "U3") (pin "25") (pinfunction "PB12_25") (pintype "passive"))
    )
    (net (code "87") (name "unconnected-(U3-PB13-Pad26)") (class "Default")
      (node (ref "U3") (pin "26") (pinfunction "PB13_26") (pintype "passive"))
    )
    (net (code "88") (name "unconnected-(U3-PB15-Pad28)") (class "Default")
      (node (ref "U3") (pin "28") (pinfunction "PB15_28") (pintype "passive"))
    )
    (net (code "89") (name "unconnected-(U3-PC13-Pad2)") (class "Default")
      (node (ref "U3") (pin "2") (pinfunction "PC13_2") (pintype "passive"))
    )
    (net (code "90") (name "unconnected-(U3-UART_CK-Pad29)") (class "Default")
      (node (ref "U3") (pin "29") (pinfunction "UART_CK_29") (pintype "passive"))
    )
    (net (code "91") (name "unconnected-(U3-UART_RX-Pad31)") (class "Default")
      (node (ref "U3") (pin "31") (pinfunction "UART_RX_31") (pintype "passive"))
    )
    (net (code "92") (name "unconnected-(U3-UART_TX-Pad30)") (class "Default")
      (node (ref "U3") (pin "30") (pinfunction "UART_TX_30") (pintype "passive"))
    )
    (net (code "93") (name "unconnected-(U3-VBAT-Pad1)") (class "Default")
      (node (ref "U3") (pin "1") (pinfunction "VBAT_1") (pintype "passive"))
    )
    (net (code "94") (name "unconnected-(U4-FT{slash}OUT-Pad7)") (class "Default")
      (node (ref "U4") (pin "7") (pinfunction "FT/OUT_7") (pintype "passive"))
    )
    (net (code "95") (name "unconnected-(U5-NC-Pad6)") (class "Default")
      (node (ref "U5") (pin "6") (pinfunction "NC_6") (pintype "passive+no_connect"))
    )
  )
)
